# StyroCutter-555-heatsink-5V.net
KiCad netlist of a schematic drawn in EAGLE
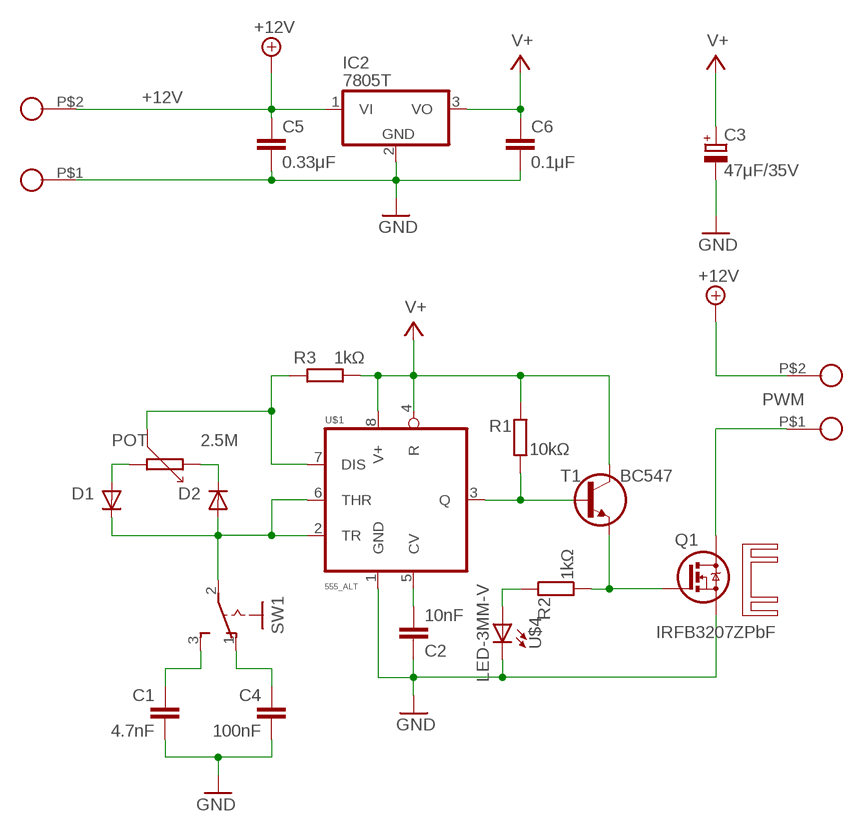
[diagram p0: schematic, sheet 1]

(export (version "E")
  (design (tool "Eeschema 10.0.6"))
  (components
    (comp (ref "C1")
      (value "4.7nF")
      (footprint "eagle-import:C050-020X036")
      (libsource (lib "eagle-import") (part "C050-020X036"))
    )
    (comp (ref "C2")
      (value "10nF")
      (footprint "eagle-import:C050-020X036")
      (libsource (lib "eagle-import") (part "C050-020X036"))
    )
    (comp (ref "C3")
      (value "47μF/35V")
      (footprint "eagle-import:E2,5-5")
      (libsource (lib "eagle-import") (part "CPOL-EUE2.5-5"))
    )
    (comp (ref "C4")
      (value "100nF")
      (footprint "eagle-import:C050-020X036")
      (libsource (lib "eagle-import") (part "C050-020X036"))
    )
    (comp (ref "C5")
      (value "0.33μF")
      (footprint "eagle-import:C050-024X044")
      (libsource (lib "eagle-import") (part "C050-024X044"))
    )
    (comp (ref "C6")
      (value "0.1μF")
      (footprint "eagle-import:C050-024X044")
      (libsource (lib "eagle-import") (part "C050-024X044"))
    )
    (comp (ref "D1")
      (value "1N4148")
      (footprint "eagle-import:DO34-7")
      (libsource (lib "eagle-import") (part "1N414834-7"))
    )
    (comp (ref "D2")
      (value "1N4148")
      (footprint "eagle-import:DO34-7")
      (libsource (lib "eagle-import") (part "1N414834-7"))
    )
    (comp (ref "IC2")
      (value "7805T")
      (footprint "eagle-import:TO220H")
      (libsource (lib "eagle-import") (part "78T05"))
    )
    (comp (ref "J1")
      (value "TERM-2")
      (footprint "eagle-import:SCREWTERM-2")
      (libsource (lib "eagle-import") (part "TERM-2"))
    )
    (comp (ref "J2")
      (value "TERM-2")
      (footprint "eagle-import:SCREWTERM-2")
      (libsource (lib "eagle-import") (part "TERM-2"))
    )
    (comp (ref "POT")
      (value "2.5M")
      (footprint "eagle-import:PC16S")
      (libsource (lib "eagle-import") (part "PIHER-PT16S"))
    )
    (comp (ref "Q1")
      (value "IRFB3207ZPbF")
      (footprint "eagle-import:TO220BV")
      (libsource (lib "eagle-import") (part "PMOSFET_NTO220BV"))
    )
    (comp (ref "R1")
      (value "10kΩ")
      (footprint "eagle-import:0204_12")
      (libsource (lib "eagle-import") (part "R0204/12"))
    )
    (comp (ref "R2")
      (value "1kΩ")
      (footprint "eagle-import:0204_10")
      (libsource (lib "eagle-import") (part "R0204/10"))
    )
    (comp (ref "R3")
      (value "1kΩ")
      (footprint "eagle-import:0202_2V")
      (libsource (lib "eagle-import") (part "R0202/2V"))
    )
    (comp (ref "SW1")
      (value "SL-SW-1P-2T-V")
      (footprint "eagle-import:SLSW-1P2T-V")
      (libsource (lib "eagle-import") (part "SL-SW-1P-2T-V"))
    )
    (comp (ref "T1")
      (value "BC547")
      (footprint "eagle-import:TO92-CBE")
      (libsource (lib "eagle-import") (part "BC547CBE"))
    )
    (comp (ref "U$1")
      (value "555_ALT")
      (footprint "eagle-import:DIL08")
      (libsource (lib "eagle-import") (part "555_ALT"))
    )
    (comp (ref "U$2")
      (value "AQ-SO")
      (footprint "eagle-import:AQ_HS_3A_SO")
      (libsource (lib "eagle-import") (part "AQ-SO"))
    )
    (comp (ref "U$4")
      (value "LED-3MM-V")
      (footprint "eagle-import:LED-3MM-V")
      (libsource (lib "eagle-import") (part "LED-3MM-V"))
    )
  )
  (nets
    (net (code "1") (name "+12V") (class "Default")
      (node (ref "C5") (pin "1") (pinfunction "1_1") (pintype "passive"))
      (node (ref "IC2") (pin "1") (pinfunction "VI_1") (pintype "input"))
      (node (ref "J1") (pin "P$2") (pinfunction "P$1_P$2") (pintype "bidirectional"))
      (node (ref "J2") (pin "P$2") (pinfunction "P$1_P$2") (pintype "bidirectional"))
    )
    (net (code "2") (name "/PWM") (class "Default")
      (node (ref "J2") (pin "P$1") (pinfunction "P$1_P$1") (pintype "bidirectional"))
      (node (ref "Q1") (pin "D") (pinfunction "D_D") (pintype "passive"))
    )
    (net (code "3") (name "GND") (class "Default")
      (node (ref "C1") (pin "2") (pinfunction "2_2") (pintype "passive"))
      (node (ref "C2") (pin "1") (pinfunction "1_1") (pintype "passive"))
      (node (ref "C3") (pin "-") (pinfunction "-_-") (pintype "passive"))
      (node (ref "C4") (pin "2") (pinfunction "2_2") (pintype "passive"))
      (node (ref "C5") (pin "2") (pinfunction "2_2") (pintype "passive"))
      (node (ref "C6") (pin "2") (pinfunction "2_2") (pintype "passive"))
      (node (ref "IC2") (pin "2") (pinfunction "GND_2") (pintype "passive"))
      (node (ref "J1") (pin "P$1") (pinfunction "P$1_P$1") (pintype "bidirectional"))
      (node (ref "Q1") (pin "S") (pinfunction "S_S") (pintype "passive"))
      (node (ref "U$1") (pin "1") (pinfunction "GND_1") (pintype "power_in"))
      (node (ref "U$4") (pin "C") (pinfunction "C_C") (pintype "passive"))
    )
    (net (code "4") (name "Net-(D1-PadA)") (class "Default")
      (node (ref "D1") (pin "A") (pinfunction "A_A") (pintype "passive"))
      (node (ref "POT") (pin "1E") (pinfunction "1E_1E") (pintype "passive"))
    )
    (net (code "5") (name "Net-(D2-PadC)") (class "Default")
      (node (ref "D2") (pin "C") (pinfunction "C_C") (pintype "passive"))
      (node (ref "POT") (pin "1A") (pinfunction "1A_1A") (pintype "passive"))
    )
    (net (code "6") (name "Net-(Q1-PadG)") (class "Default")
      (node (ref "Q1") (pin "G") (pinfunction "G_G") (pintype "passive"))
      (node (ref "R2") (pin "1") (pinfunction "1_1") (pintype "passive"))
      (node (ref "T1") (pin "E") (pinfunction "E_E") (pintype "passive"))
    )
    (net (code "7") (name "Net-(R2-Pad2)") (class "Default")
      (node (ref "R2") (pin "2") (pinfunction "2_2") (pintype "passive"))
      (node (ref "U$4") (pin "A") (pinfunction "A_A") (pintype "passive"))
    )
    (net (code "8") (name "Net-(SW1-O)") (class "Default")
      (node (ref "C4") (pin "1") (pinfunction "1_1") (pintype "passive"))
      (node (ref "SW1") (pin "1") (pinfunction "O_1") (pintype "passive"))
    )
    (net (code "9") (name "Net-(SW1-P)") (class "Default")
      (node (ref "D1") (pin "C") (pinfunction "C_C") (pintype "passive"))
      (node (ref "D2") (pin "A") (pinfunction "A_A") (pintype "passive"))
      (node (ref "SW1") (pin "2") (pinfunction "P_2") (pintype "passive"))
      (node (ref "U$1") (pin "2") (pinfunction "TR_2") (pintype "input"))
      (node (ref "U$1") (pin "6") (pinfunction "THR_6") (pintype "input"))
    )
    (net (code "10") (name "Net-(SW1-S)") (class "Default")
      (node (ref "C1") (pin "1") (pinfunction "1_1") (pintype "passive"))
      (node (ref "SW1") (pin "3") (pinfunction "S_3") (pintype "passive"))
    )
    (net (code "11") (name "Net-(U$1-CV)") (class "Default")
      (node (ref "C2") (pin "2") (pinfunction "2_2") (pintype "passive"))
      (node (ref "U$1") (pin "5") (pinfunction "CV_5") (pintype "input"))
    )
    (net (code "12") (name "Net-(U$1-DIS)") (class "Default")
      (node (ref "POT") (pin "1S") (pinfunction "1S_1S") (pintype "passive"))
      (node (ref "R3") (pin "1") (pinfunction "1_1") (pintype "passive"))
      (node (ref "U$1") (pin "7") (pinfunction "DIS_7") (pintype "passive"))
    )
    (net (code "13") (name "Net-(U$1-Q)") (class "Default")
      (node (ref "R1") (pin "1") (pinfunction "1_1") (pintype "passive"))
      (node (ref "T1") (pin "B") (pinfunction "B_B") (pintype "passive"))
      (node (ref "U$1") (pin "3") (pinfunction "Q_3") (pintype "output"))
    )
    (net (code "14") (name "V+") (class "Default")
      (node (ref "C3") (pin "+") (pinfunction "+_+") (pintype "passive"))
      (node (ref "C6") (pin "1") (pinfunction "1_1") (pintype "passive"))
      (node (ref "IC2") (pin "3") (pinfunction "VO_3") (pintype "passive"))
      (node (ref "R1") (pin "2") (pinfunction "2_2") (pintype "passive"))
      (node (ref "R3") (pin "2") (pinfunction "2_2") (pintype "passive"))
      (node (ref "T1") (pin "C") (pinfunction "C_C") (pintype "passive"))
      (node (ref "U$1") (pin "4") (pinfunction "R_4") (pintype "input"))
      (node (ref "U$1") (pin "8") (pinfunction "V+_8") (pintype "power_in"))
    )
  )
)
